# stm_power_supply.net
KiCad netlist of a schematic drawn in EAGLE
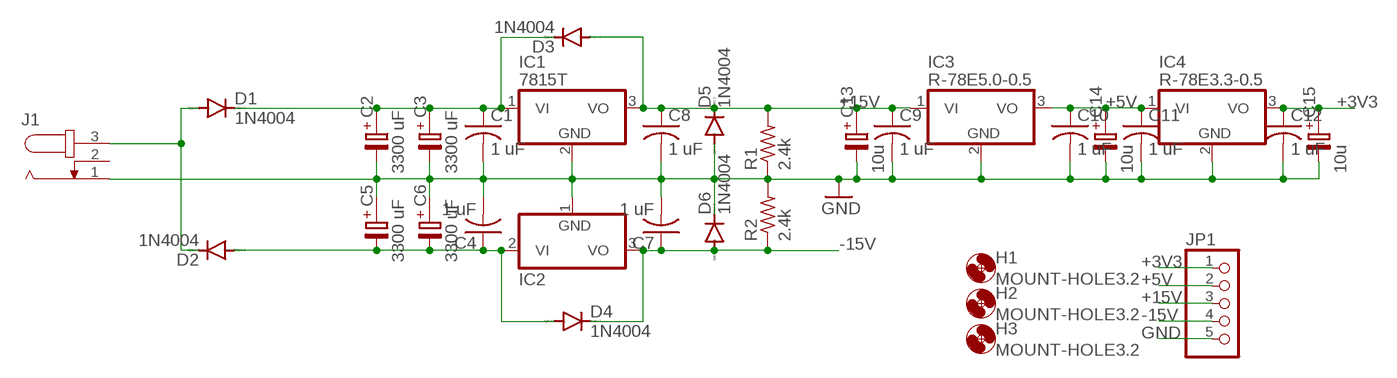
[diagram p0: schematic, sheet 1]

(export (version "E")
  (design (tool "Eeschema 10.0.6"))
  (components
    (comp (ref "C1")
      (value "1 uF")
      (footprint "eagle-import:C025-024X044")
      (libsource (lib "eagle-import") (part "C-US025-024X044"))
    )
    (comp (ref "C2")
      (value "3300 uF")
      (footprint "eagle-import:E7,5-18")
      (libsource (lib "eagle-import") (part "C-PR-7,5X18"))
    )
    (comp (ref "C3")
      (value "3300 uF")
      (footprint "eagle-import:E7,5-18")
      (libsource (lib "eagle-import") (part "C-PR-7,5X18"))
    )
    (comp (ref "C4")
      (value "1 uF")
      (footprint "eagle-import:C025-024X044")
      (libsource (lib "eagle-import") (part "C-US025-024X044"))
    )
    (comp (ref "C5")
      (value "3300 uF")
      (footprint "eagle-import:E7,5-18")
      (libsource (lib "eagle-import") (part "C-PR-7,5X18"))
    )
    (comp (ref "C6")
      (value "3300 uF")
      (footprint "eagle-import:E7,5-18")
      (libsource (lib "eagle-import") (part "C-PR-7,5X18"))
    )
    (comp (ref "C7")
      (value "1 uF")
      (footprint "eagle-import:C025-024X044")
      (libsource (lib "eagle-import") (part "C-US025-024X044"))
    )
    (comp (ref "C8")
      (value "1 uF")
      (footprint "eagle-import:C025-024X044")
      (libsource (lib "eagle-import") (part "C-US025-024X044"))
    )
    (comp (ref "C9")
      (value "1 uF")
      (footprint "eagle-import:C025-024X044")
      (libsource (lib "eagle-import") (part "C-US025-024X044"))
    )
    (comp (ref "C10")
      (value "1 uF")
      (footprint "eagle-import:C025-024X044")
      (libsource (lib "eagle-import") (part "C-US025-024X044"))
    )
    (comp (ref "C11")
      (value "1 uF")
      (footprint "eagle-import:C025-024X044")
      (libsource (lib "eagle-import") (part "C-US025-024X044"))
    )
    (comp (ref "C12")
      (value "1 uF")
      (footprint "eagle-import:C025-024X044")
      (libsource (lib "eagle-import") (part "C-US025-024X044"))
    )
    (comp (ref "C13")
      (value "10u")
      (footprint "eagle-import:E2,5-6")
      (libsource (lib "eagle-import") (part "C-PR-2,5X6"))
    )
    (comp (ref "C14")
      (value "10u")
      (footprint "eagle-import:E2,5-6")
      (libsource (lib "eagle-import") (part "C-PR-2,5X6"))
    )
    (comp (ref "C15")
      (value "10u")
      (footprint "eagle-import:E2,5-6")
      (libsource (lib "eagle-import") (part "C-PR-2,5X6"))
    )
    (comp (ref "D1")
      (value "1N4004")
      (footprint "eagle-import:DO41-10")
      (libsource (lib "eagle-import") (part "1N4004"))
    )
    (comp (ref "D2")
      (value "1N4004")
      (footprint "eagle-import:DO41-10")
      (libsource (lib "eagle-import") (part "1N4004"))
    )
    (comp (ref "D3")
      (value "1N4004")
      (footprint "eagle-import:DO41-10")
      (libsource (lib "eagle-import") (part "1N4004"))
    )
    (comp (ref "D4")
      (value "1N4004")
      (footprint "eagle-import:DO41-10")
      (libsource (lib "eagle-import") (part "1N4004"))
    )
    (comp (ref "D5")
      (value "1N4004")
      (footprint "eagle-import:DO41-10")
      (libsource (lib "eagle-import") (part "1N4004"))
    )
    (comp (ref "D6")
      (value "1N4004")
      (footprint "eagle-import:DO41-10")
      (libsource (lib "eagle-import") (part "1N4004"))
    )
    (comp (ref "H1")
      (value "MOUNT-HOLE3.2")
      (footprint "eagle-import:3,2")
      (libsource (lib "eagle-import") (part "MOUNT-HOLE3.2"))
    )
    (comp (ref "H2")
      (value "MOUNT-HOLE3.2")
      (footprint "eagle-import:3,2")
      (libsource (lib "eagle-import") (part "MOUNT-HOLE3.2"))
    )
    (comp (ref "H3")
      (value "MOUNT-HOLE3.2")
      (footprint "eagle-import:3,2")
      (libsource (lib "eagle-import") (part "MOUNT-HOLE3.2"))
    )
    (comp (ref "IC1")
      (value "7815T")
      (footprint "eagle-import:TO220H")
      (libsource (lib "eagle-import") (part "78T15"))
    )
    (comp (ref "IC2")
      (value "7915T")
      (footprint "eagle-import:TO220H")
      (libsource (lib "eagle-import") (part "79T15"))
    )
    (comp (ref "IC3")
      (value "R-78E5.0-0.5")
      (footprint "eagle-import:WE78")
      (libsource (lib "eagle-import") (part "WE173950378"))
    )
    (comp (ref "IC4")
      (value "R-78E3.3-0.5")
      (footprint "eagle-import:WE78")
      (libsource (lib "eagle-import") (part "WE173950378"))
    )
    (comp (ref "J1")
      (value "JACK-PLUG0")
      (footprint "eagle-import:SPC4077")
      (libsource (lib "eagle-import") (part "JACK-PLUG0"))
    )
    (comp (ref "JP1")
      (value "PINHD-1X5")
      (footprint "eagle-import:1X05")
      (libsource (lib "eagle-import") (part "PINHD-1X5"))
    )
    (comp (ref "R1")
      (value "2.4k")
      (footprint "eagle-import:0204_7")
      (libsource (lib "eagle-import") (part "R-US_0204/7"))
    )
    (comp (ref "R2")
      (value "2.4k")
      (footprint "eagle-import:0204_7")
      (libsource (lib "eagle-import") (part "R-US_0204/7"))
    )
  )
  (nets
    (net (code "1") (name "/+3V3") (class "Default")
      (node (ref "C12") (pin "1") (pinfunction "1_1") (pintype "passive"))
      (node (ref "C15") (pin "+") (pinfunction "+_+") (pintype "passive"))
      (node (ref "IC4") (pin "3") (pinfunction "VO_3") (pintype "passive"))
      (node (ref "JP1") (pin "1") (pinfunction "1_1") (pintype "passive"))
    )
    (net (code "2") (name "/+5V") (class "Default")
      (node (ref "C10") (pin "1") (pinfunction "1_1") (pintype "passive"))
      (node (ref "C11") (pin "1") (pinfunction "1_1") (pintype "passive"))
      (node (ref "C14") (pin "+") (pinfunction "+_+") (pintype "passive"))
      (node (ref "IC3") (pin "3") (pinfunction "VO_3") (pintype "passive"))
      (node (ref "IC4") (pin "1") (pinfunction "VI_1") (pintype "input"))
      (node (ref "JP1") (pin "2") (pinfunction "2_2") (pintype "passive"))
    )
    (net (code "3") (name "/+15V") (class "Default")
      (node (ref "C13") (pin "+") (pinfunction "+_+") (pintype "passive"))
      (node (ref "C8") (pin "1") (pinfunction "1_1") (pintype "passive"))
      (node (ref "C9") (pin "1") (pinfunction "1_1") (pintype "passive"))
      (node (ref "D3") (pin "A") (pinfunction "A_A") (pintype "passive"))
      (node (ref "D5") (pin "C") (pinfunction "C_C") (pintype "passive"))
      (node (ref "IC1") (pin "3") (pinfunction "VO_3") (pintype "passive"))
      (node (ref "IC3") (pin "1") (pinfunction "VI_1") (pintype "input"))
      (node (ref "JP1") (pin "3") (pinfunction "3_3") (pintype "passive"))
      (node (ref "R1") (pin "2") (pinfunction "2_2") (pintype "passive"))
    )
    (net (code "4") (name "/-15V") (class "Default")
      (node (ref "C7") (pin "1") (pinfunction "1_1") (pintype "passive"))
      (node (ref "D4") (pin "C") (pinfunction "C_C") (pintype "passive"))
      (node (ref "D6") (pin "A") (pinfunction "A_A") (pintype "passive"))
      (node (ref "IC2") (pin "3") (pinfunction "VO_3") (pintype "passive"))
      (node (ref "JP1") (pin "4") (pinfunction "4_4") (pintype "passive"))
      (node (ref "R2") (pin "1") (pinfunction "1_1") (pintype "passive"))
    )
    (net (code "5") (name "GND") (class "Default")
      (node (ref "C1") (pin "2") (pinfunction "2_2") (pintype "passive"))
      (node (ref "C10") (pin "2") (pinfunction "2_2") (pintype "passive"))
      (node (ref "C11") (pin "2") (pinfunction "2_2") (pintype "passive"))
      (node (ref "C12") (pin "2") (pinfunction "2_2") (pintype "passive"))
      (node (ref "C13") (pin "-") (pinfunction "-_-") (pintype "passive"))
      (node (ref "C14") (pin "-") (pinfunction "-_-") (pintype "passive"))
      (node (ref "C15") (pin "-") (pinfunction "-_-") (pintype "passive"))
      (node (ref "C2") (pin "-") (pinfunction "-_-") (pintype "passive"))
      (node (ref "C3") (pin "-") (pinfunction "-_-") (pintype "passive"))
      (node (ref "C4") (pin "2") (pinfunction "2_2") (pintype "passive"))
      (node (ref "C5") (pin "+") (pinfunction "+_+") (pintype "passive"))
      (node (ref "C6") (pin "+") (pinfunction "+_+") (pintype "passive"))
      (node (ref "C7") (pin "2") (pinfunction "2_2") (pintype "passive"))
      (node (ref "C8") (pin "2") (pinfunction "2_2") (pintype "passive"))
      (node (ref "C9") (pin "2") (pinfunction "2_2") (pintype "passive"))
      (node (ref "D5") (pin "A") (pinfunction "A_A") (pintype "passive"))
      (node (ref "D6") (pin "C") (pinfunction "C_C") (pintype "passive"))
      (node (ref "IC1") (pin "2") (pinfunction "GND_2") (pintype "passive"))
      (node (ref "IC2") (pin "1") (pinfunction "GND_1") (pintype "passive"))
      (node (ref "IC3") (pin "2") (pinfunction "GND_2") (pintype "passive"))
      (node (ref "IC4") (pin "2") (pinfunction "GND_2") (pintype "passive"))
      (node (ref "J1") (pin "1") (pinfunction "1_1") (pintype "passive"))
      (node (ref "JP1") (pin "5") (pinfunction "5_5") (pintype "passive"))
      (node (ref "R1") (pin "1") (pinfunction "1_1") (pintype "passive"))
      (node (ref "R2") (pin "2") (pinfunction "2_2") (pintype "passive"))
    )
    (net (code "6") (name "Net-(D1-PadA)") (class "Default")
      (node (ref "D1") (pin "A") (pinfunction "A_A") (pintype "passive"))
      (node (ref "D2") (pin "C") (pinfunction "C_C") (pintype "passive"))
      (node (ref "J1") (pin "3") (pinfunction "3_3") (pintype "passive"))
    )
    (net (code "7") (name "Net-(IC1-VI)") (class "Default")
      (node (ref "C1") (pin "1") (pinfunction "1_1") (pintype "passive"))
      (node (ref "C2") (pin "+") (pinfunction "+_+") (pintype "passive"))
      (node (ref "C3") (pin "+") (pinfunction "+_+") (pintype "passive"))
      (node (ref "D1") (pin "C") (pinfunction "C_C") (pintype "passive"))
      (node (ref "D3") (pin "C") (pinfunction "C_C") (pintype "passive"))
      (node (ref "IC1") (pin "1") (pinfunction "VI_1") (pintype "input"))
    )
    (net (code "8") (name "Net-(IC2-VI)") (class "Default")
      (node (ref "C4") (pin "1") (pinfunction "1_1") (pintype "passive"))
      (node (ref "C5") (pin "-") (pinfunction "-_-") (pintype "passive"))
      (node (ref "C6") (pin "-") (pinfunction "-_-") (pintype "passive"))
      (node (ref "D2") (pin "A") (pinfunction "A_A") (pintype "passive"))
      (node (ref "D4") (pin "A") (pinfunction "A_A") (pintype "passive"))
      (node (ref "IC2") (pin "2") (pinfunction "VI_2") (pintype "input"))
    )
    (net (code "9") (name "unconnected-(J1-Pad2)") (class "Default")
      (node (ref "J1") (pin "2") (pinfunction "2_2") (pintype "passive"))
    )
  )
)
